# train_module.net
KiCad netlist of a schematic drawn in EAGLE
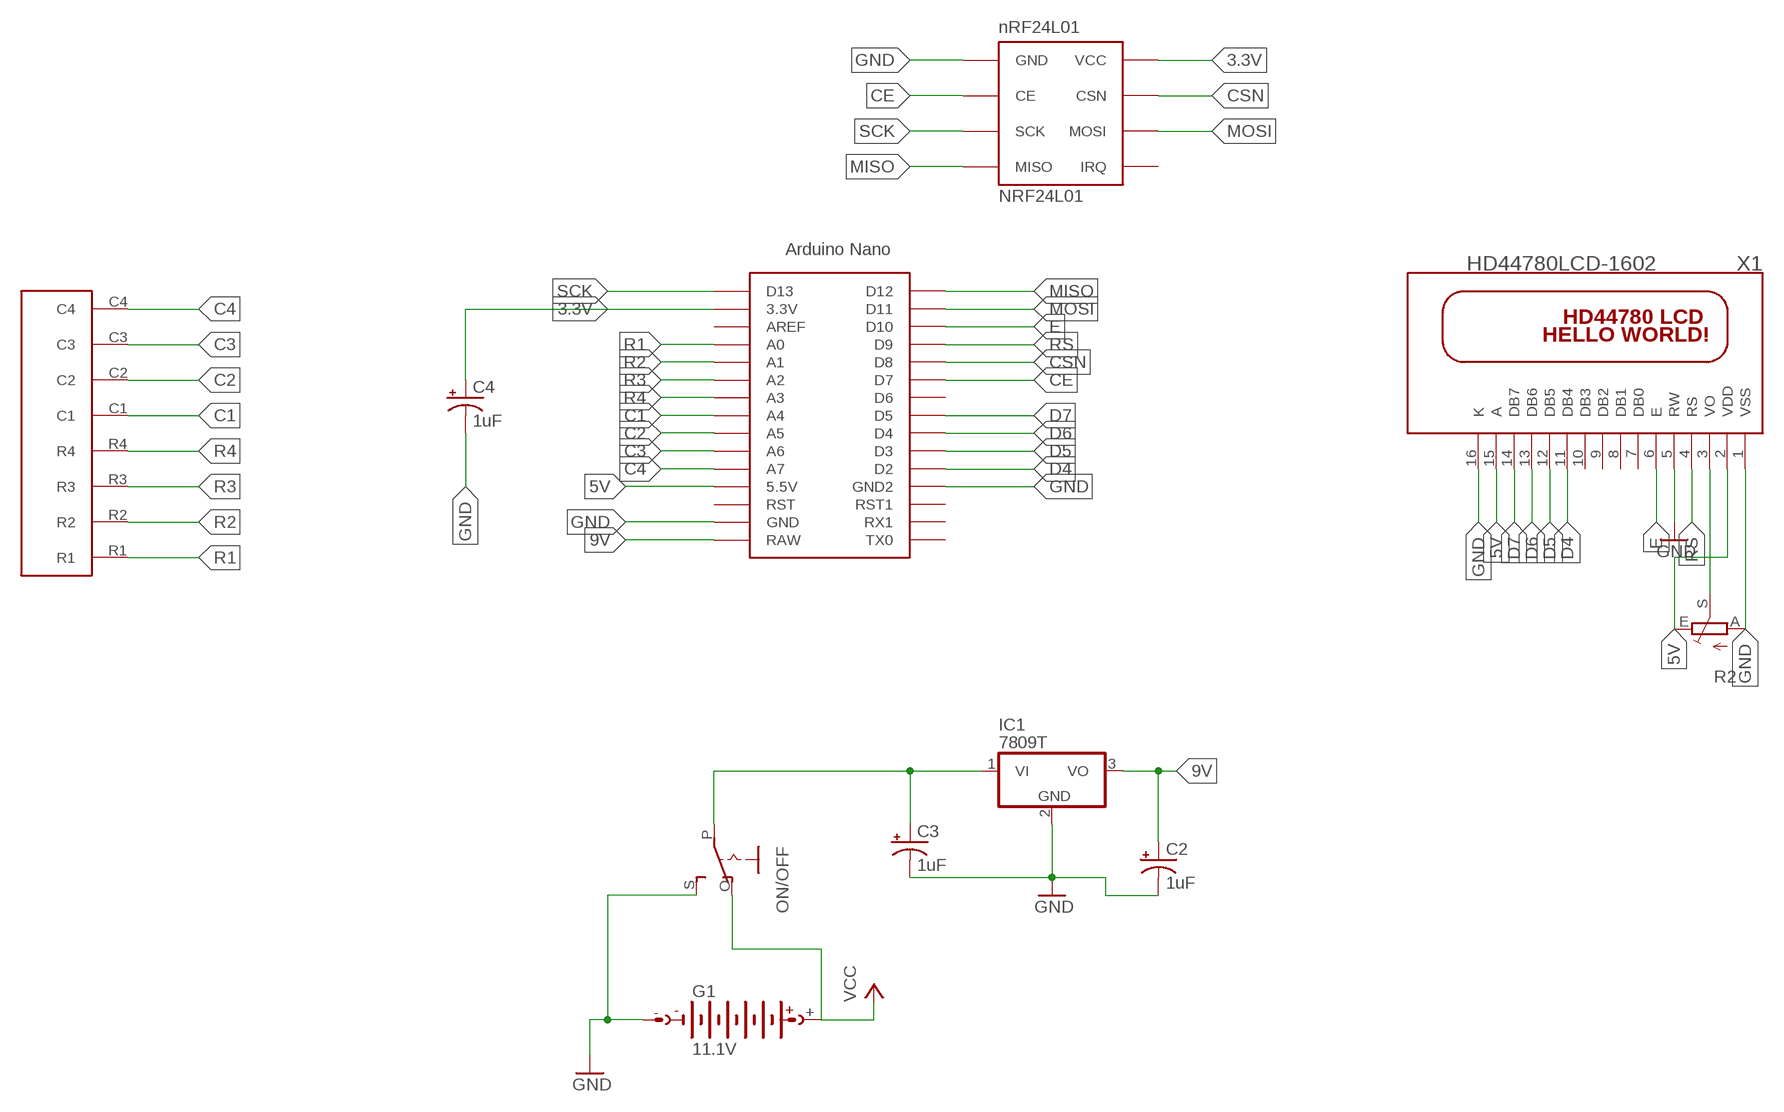
[diagram p0: schematic, sheet 1]

(export (version "E")
  (design (tool "Eeschema 10.0.6"))
  (components
    (comp (ref "C2")
      (value "1uF")
      (footprint "eagle-import:E2,5-7")
      (libsource (lib "eagle-import") (part "CPOL-USE2.5-7"))
    )
    (comp (ref "C3")
      (value "1uF")
      (footprint "eagle-import:E2,5-7")
      (libsource (lib "eagle-import") (part "CPOL-USE2.5-7"))
    )
    (comp (ref "C4")
      (value "1uF")
      (footprint "eagle-import:E2,5-7")
      (libsource (lib "eagle-import") (part "CPOL-USE2.5-7"))
    )
    (comp (ref "G1")
      (value "11.1V")
      (footprint "eagle-import:AB9V")
      (libsource (lib "eagle-import") (part "AB9V"))
    )
    (comp (ref "IC1")
      (value "7809T")
      (footprint "eagle-import:TO220V")
      (libsource (lib "eagle-import") (part "78TV05"))
    )
    (comp (ref "NRF24L1")
      (value "NRF24L01")
      (footprint "eagle-import:NRF24L01")
      (libsource (lib "eagle-import") (part "NRF24L01"))
    )
    (comp (ref "ON/OFF")
      (value "EG1218S")
      (footprint "eagle-import:EG1218")
      (libsource (lib "eagle-import") (part "EG1218S"))
    )
    (comp (ref "R2")
      (value "TRIM_EU-CA9V")
      (footprint "eagle-import:CA9V")
      (libsource (lib "eagle-import") (part "TRIM_EU-CA9V"))
    )
    (comp (ref "U$1")
      (value "NANO")
      (footprint "eagle-import:NANO")
      (libsource (lib "eagle-import") (part "NANO"))
    )
    (comp (ref "U$2")
      (value "KEYPAD")
      (footprint "eagle-import:KEYPAD")
      (libsource (lib "eagle-import") (part "KEYPAD"))
    )
    (comp (ref "X1")
      (value "HD44780LCD-1602")
      (footprint "eagle-import:LCD1602")
      (libsource (lib "eagle-import") (part "HD44780LCD-1602"))
    )
  )
  (nets
    (net (code "1") (name "3.3V") (class "Default")
      (node (ref "C4") (pin "+") (pinfunction "+_+") (pintype "passive"))
      (node (ref "NRF24L1") (pin "VCC") (pinfunction "VCC_VCC") (pintype "bidirectional"))
      (node (ref "U$1") (pin "3.3V") (pinfunction "3.3V_3.3V") (pintype "bidirectional"))
    )
    (net (code "2") (name "5V") (class "Default")
      (node (ref "R2") (pin "E") (pinfunction "E_E") (pintype "passive"))
      (node (ref "U$1") (pin "5V") (pinfunction "5.5V_5V") (pintype "bidirectional"))
      (node (ref "X1") (pin "15") (pinfunction "A_15") (pintype "input"))
      (node (ref "X1") (pin "2") (pinfunction "VDD_2") (pintype "power_in"))
    )
    (net (code "3") (name "9V") (class "Default")
      (node (ref "C2") (pin "+") (pinfunction "+_+") (pintype "passive"))
      (node (ref "IC1") (pin "3") (pinfunction "VO_3") (pintype "passive"))
      (node (ref "U$1") (pin "RAW") (pinfunction "RAW_RAW") (pintype "bidirectional"))
    )
    (net (code "4") (name "C1") (class "Default")
      (node (ref "U$1") (pin "A4") (pinfunction "A4_A4") (pintype "bidirectional"))
      (node (ref "U$2") (pin "C1") (pinfunction "C1_C1") (pintype "bidirectional"))
    )
    (net (code "5") (name "C2") (class "Default")
      (node (ref "U$1") (pin "A5") (pinfunction "A5_A5") (pintype "bidirectional"))
      (node (ref "U$2") (pin "C2") (pinfunction "C2_C2") (pintype "bidirectional"))
    )
    (net (code "6") (name "C3") (class "Default")
      (node (ref "U$1") (pin "A6") (pinfunction "A6_A6") (pintype "bidirectional"))
      (node (ref "U$2") (pin "C3") (pinfunction "C3_C3") (pintype "bidirectional"))
    )
    (net (code "7") (name "C4") (class "Default")
      (node (ref "U$1") (pin "A7") (pinfunction "A7_A7") (pintype "bidirectional"))
      (node (ref "U$2") (pin "C4") (pinfunction "C4_C4") (pintype "bidirectional"))
    )
    (net (code "8") (name "CE") (class "Default")
      (node (ref "NRF24L1") (pin "CE") (pinfunction "CE_CE") (pintype "bidirectional"))
      (node (ref "U$1") (pin "D7") (pinfunction "D7_D7") (pintype "bidirectional"))
    )
    (net (code "9") (name "CSN") (class "Default")
      (node (ref "NRF24L1") (pin "CSN") (pinfunction "CSN_CSN") (pintype "bidirectional"))
      (node (ref "U$1") (pin "D8") (pinfunction "D8_D8") (pintype "bidirectional"))
    )
    (net (code "10") (name "D4") (class "Default")
      (node (ref "U$1") (pin "D2") (pinfunction "D2_D2") (pintype "bidirectional"))
      (node (ref "X1") (pin "11") (pinfunction "DB4_11") (pintype "bidirectional"))
    )
    (net (code "11") (name "D5") (class "Default")
      (node (ref "U$1") (pin "D3") (pinfunction "D3_D3") (pintype "bidirectional"))
      (node (ref "X1") (pin "12") (pinfunction "DB5_12") (pintype "bidirectional"))
    )
    (net (code "12") (name "D6") (class "Default")
      (node (ref "U$1") (pin "D4") (pinfunction "D4_D4") (pintype "bidirectional"))
      (node (ref "X1") (pin "13") (pinfunction "DB6_13") (pintype "bidirectional"))
    )
    (net (code "13") (name "D7") (class "Default")
      (node (ref "U$1") (pin "D5") (pinfunction "D5_D5") (pintype "bidirectional"))
      (node (ref "X1") (pin "14") (pinfunction "DB7_14") (pintype "bidirectional"))
    )
    (net (code "14") (name "E") (class "Default")
      (node (ref "U$1") (pin "D10") (pinfunction "D10_D10") (pintype "bidirectional"))
      (node (ref "X1") (pin "6") (pinfunction "E_6") (pintype "input"))
    )
    (net (code "15") (name "GND") (class "Default")
      (node (ref "C2") (pin "-") (pinfunction "-_-") (pintype "passive"))
      (node (ref "C3") (pin "-") (pinfunction "-_-") (pintype "passive"))
      (node (ref "C4") (pin "-") (pinfunction "-_-") (pintype "passive"))
      (node (ref "G1") (pin "-") (pinfunction "-_-") (pintype "passive"))
      (node (ref "IC1") (pin "2") (pinfunction "GND_2") (pintype "passive"))
      (node (ref "NRF24L1") (pin "GND") (pinfunction "GND_GND") (pintype "bidirectional"))
      (node (ref "ON/OFF") (pin "S") (pinfunction "S_S") (pintype "passive"))
      (node (ref "R2") (pin "A") (pinfunction "A_A") (pintype "passive"))
      (node (ref "U$1") (pin "GND") (pinfunction "GND_GND") (pintype "bidirectional"))
      (node (ref "U$1") (pin "GND1") (pinfunction "GND2_GND1") (pintype "bidirectional"))
      (node (ref "X1") (pin "1") (pinfunction "VSS_1") (pintype "power_in"))
      (node (ref "X1") (pin "16") (pinfunction "K_16") (pintype "input"))
      (node (ref "X1") (pin "5") (pinfunction "RW_5") (pintype "input"))
    )
    (net (code "16") (name "MISO") (class "Default")
      (node (ref "NRF24L1") (pin "MISO") (pinfunction "MISO_MISO") (pintype "bidirectional"))
      (node (ref "U$1") (pin "D12") (pinfunction "D12_D12") (pintype "bidirectional"))
    )
    (net (code "17") (name "MOSI") (class "Default")
      (node (ref "NRF24L1") (pin "MOSI") (pinfunction "MOSI_MOSI") (pintype "bidirectional"))
      (node (ref "U$1") (pin "D11") (pinfunction "D11_D11") (pintype "bidirectional"))
    )
    (net (code "18") (name "Net-(IC1-VI)") (class "Default")
      (node (ref "C3") (pin "+") (pinfunction "+_+") (pintype "passive"))
      (node (ref "IC1") (pin "1") (pinfunction "VI_1") (pintype "input"))
      (node (ref "ON/OFF") (pin "P") (pinfunction "P_P") (pintype "passive"))
    )
    (net (code "19") (name "Net-(X1-VO)") (class "Default")
      (node (ref "R2") (pin "S") (pinfunction "S_S") (pintype "passive"))
      (node (ref "X1") (pin "3") (pinfunction "VO_3") (pintype "input"))
    )
    (net (code "20") (name "R1") (class "Default")
      (node (ref "U$1") (pin "A0") (pinfunction "A0_A0") (pintype "bidirectional"))
      (node (ref "U$2") (pin "R1") (pinfunction "R1_R1") (pintype "bidirectional"))
    )
    (net (code "21") (name "R2") (class "Default")
      (node (ref "U$1") (pin "A1") (pinfunction "A1_A1") (pintype "bidirectional"))
      (node (ref "U$2") (pin "R2") (pinfunction "R2_R2") (pintype "bidirectional"))
    )
    (net (code "22") (name "R3") (class "Default")
      (node (ref "U$1") (pin "A2") (pinfunction "A2_A2") (pintype "bidirectional"))
      (node (ref "U$2") (pin "R3") (pinfunction "R3_R3") (pintype "bidirectional"))
    )
    (net (code "23") (name "R4") (class "Default")
      (node (ref "U$1") (pin "A3") (pinfunction "A3_A3") (pintype "bidirectional"))
      (node (ref "U$2") (pin "R4") (pinfunction "R4_R4") (pintype "bidirectional"))
    )
    (net (code "24") (name "RS") (class "Default")
      (node (ref "U$1") (pin "D9") (pinfunction "D9_D9") (pintype "bidirectional"))
      (node (ref "X1") (pin "4") (pinfunction "RS_4") (pintype "input"))
    )
    (net (code "25") (name "SCK") (class "Default")
      (node (ref "NRF24L1") (pin "SCK") (pinfunction "SCK_SCK") (pintype "bidirectional"))
      (node (ref "U$1") (pin "D13") (pinfunction "D13_D13") (pintype "bidirectional"))
    )
    (net (code "26") (name "VCC") (class "Default")
      (node (ref "G1") (pin "+") (pinfunction "+_+") (pintype "passive"))
      (node (ref "ON/OFF") (pin "O") (pinfunction "O_O") (pintype "passive"))
    )
    (net (code "27") (name "unconnected-(NRF24L1-PadIRQ)") (class "Default")
      (node (ref "NRF24L1") (pin "IRQ") (pinfunction "IRQ_IRQ") (pintype "bidirectional"))
    )
    (net (code "28") (name "unconnected-(U$1-PadAREF)") (class "Default")
      (node (ref "U$1") (pin "AREF") (pinfunction "AREF_AREF") (pintype "bidirectional"))
    )
    (net (code "29") (name "unconnected-(U$1-PadD6)") (class "Default")
      (node (ref "U$1") (pin "D6") (pinfunction "D6_D6") (pintype "bidirectional"))
    )
    (net (code "30") (name "unconnected-(U$1-PadRST)") (class "Default")
      (node (ref "U$1") (pin "RST") (pinfunction "RST_RST") (pintype "bidirectional"))
    )
    (net (code "31") (name "unconnected-(U$1-PadRST1)") (class "Default")
      (node (ref "U$1") (pin "RST1") (pinfunction "RST1_RST1") (pintype "bidirectional"))
    )
    (net (code "32") (name "unconnected-(U$1-PadRX1)") (class "Default")
      (node (ref "U$1") (pin "RX1") (pinfunction "RX1_RX1") (pintype "bidirectional"))
    )
    (net (code "33") (name "unconnected-(U$1-PadTX0)") (class "Default")
      (node (ref "U$1") (pin "TX0") (pinfunction "TX0_TX0") (pintype "bidirectional"))
    )
    (net (code "34") (name "unconnected-(X1-DB0-Pad7)") (class "Default")
      (node (ref "X1") (pin "7") (pinfunction "DB0_7") (pintype "bidirectional"))
    )
    (net (code "35") (name "unconnected-(X1-DB1-Pad8)") (class "Default")
      (node (ref "X1") (pin "8") (pinfunction "DB1_8") (pintype "bidirectional"))
    )
    (net (code "36") (name "unconnected-(X1-DB2-Pad9)") (class "Default")
      (node (ref "X1") (pin "9") (pinfunction "DB2_9") (pintype "bidirectional"))
    )
    (net (code "37") (name "unconnected-(X1-DB3-Pad10)") (class "Default")
      (node (ref "X1") (pin "10") (pinfunction "DB3_10") (pintype "bidirectional"))
    )
  )
)
